# rj45UsbBreakout.net
KiCad netlist of a schematic drawn in EAGLE
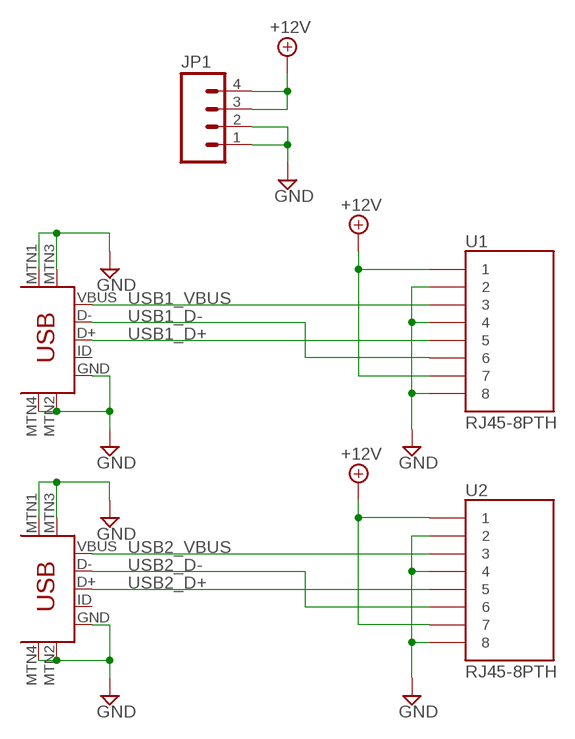
[diagram p0: schematic, sheet 1]

(export (version "E")
  (design (tool "Eeschema 10.0.6"))
  (components
    (comp (ref "JP1")
      (value "M04LOCK")
      (footprint "eagle-import:1X04_LOCK")
      (libsource (lib "eagle-import") (part "M04LOCK"))
    )
    (comp (ref "U1")
      (value "RJ45-8PTH")
      (footprint "eagle-import:RJ45-8")
      (libsource (lib "eagle-import") (part "RJ45-8PTH"))
    )
    (comp (ref "U2")
      (value "RJ45-8PTH")
      (footprint "eagle-import:RJ45-8")
      (libsource (lib "eagle-import") (part "RJ45-8PTH"))
    )
    (comp (ref "U3")
      (value "USB-MINIB-5PIN")
      (footprint "eagle-import:USB-MINIB")
      (libsource (lib "eagle-import") (part "USB-MINIB-5PIN"))
    )
    (comp (ref "U4")
      (value "USB-MINIB-5PIN")
      (footprint "eagle-import:USB-MINIB")
      (libsource (lib "eagle-import") (part "USB-MINIB-5PIN"))
    )
  )
  (nets
    (net (code "1") (name "+12V") (class "Default")
      (node (ref "JP1") (pin "3") (pinfunction "3_3") (pintype "passive"))
      (node (ref "JP1") (pin "4") (pinfunction "4_4") (pintype "passive"))
      (node (ref "U1") (pin "1") (pinfunction "1_1") (pintype "bidirectional"))
      (node (ref "U1") (pin "7") (pinfunction "7_7") (pintype "bidirectional"))
      (node (ref "U2") (pin "1") (pinfunction "1_1") (pintype "bidirectional"))
      (node (ref "U2") (pin "7") (pinfunction "7_7") (pintype "bidirectional"))
    )
    (net (code "2") (name "/USB1_D+") (class "Default")
      (node (ref "U1") (pin "5") (pinfunction "5_5") (pintype "bidirectional"))
      (node (ref "U3") (pin "D+") (pinfunction "D+_D+") (pintype "bidirectional"))
    )
    (net (code "3") (name "/USB1_D-") (class "Default")
      (node (ref "U1") (pin "6") (pinfunction "6_6") (pintype "bidirectional"))
      (node (ref "U3") (pin "D-") (pinfunction "D-_D-") (pintype "bidirectional"))
    )
    (net (code "4") (name "/USB1_VBUS") (class "Default")
      (node (ref "U1") (pin "3") (pinfunction "3_3") (pintype "bidirectional"))
      (node (ref "U3") (pin "VBUS") (pinfunction "VBUS_VBUS") (pintype "bidirectional"))
    )
    (net (code "5") (name "/USB2_D+") (class "Default")
      (node (ref "U2") (pin "5") (pinfunction "5_5") (pintype "bidirectional"))
      (node (ref "U4") (pin "D+") (pinfunction "D+_D+") (pintype "bidirectional"))
    )
    (net (code "6") (name "/USB2_D-") (class "Default")
      (node (ref "U2") (pin "6") (pinfunction "6_6") (pintype "bidirectional"))
      (node (ref "U4") (pin "D-") (pinfunction "D-_D-") (pintype "bidirectional"))
    )
    (net (code "7") (name "/USB2_VBUS") (class "Default")
      (node (ref "U2") (pin "3") (pinfunction "3_3") (pintype "bidirectional"))
      (node (ref "U4") (pin "VBUS") (pinfunction "VBUS_VBUS") (pintype "bidirectional"))
    )
    (net (code "8") (name "GND") (class "Default")
      (node (ref "JP1") (pin "1") (pinfunction "1_1") (pintype "passive"))
      (node (ref "JP1") (pin "2") (pinfunction "2_2") (pintype "passive"))
      (node (ref "U1") (pin "2") (pinfunction "2_2") (pintype "bidirectional"))
      (node (ref "U1") (pin "4") (pinfunction "4_4") (pintype "bidirectional"))
      (node (ref "U1") (pin "8") (pinfunction "8_8") (pintype "bidirectional"))
      (node (ref "U2") (pin "2") (pinfunction "2_2") (pintype "bidirectional"))
      (node (ref "U2") (pin "4") (pinfunction "4_4") (pintype "bidirectional"))
      (node (ref "U2") (pin "8") (pinfunction "8_8") (pintype "bidirectional"))
      (node (ref "U3") (pin "GND") (pinfunction "GND_GND") (pintype "bidirectional"))
      (node (ref "U3") (pin "MTN1") (pinfunction "MTN2_MTN1") (pintype "bidirectional"))
      (node (ref "U3") (pin "MTN2") (pinfunction "MTN3_MTN2") (pintype "bidirectional"))
      (node (ref "U3") (pin "MTN3") (pinfunction "MTN1_MTN3") (pintype "bidirectional"))
      (node (ref "U3") (pin "MTN4") (pinfunction "MTN4_MTN4") (pintype "bidirectional"))
      (node (ref "U4") (pin "GND") (pinfunction "GND_GND") (pintype "bidirectional"))
      (node (ref "U4") (pin "MTN1") (pinfunction "MTN2_MTN1") (pintype "bidirectional"))
      (node (ref "U4") (pin "MTN2") (pinfunction "MTN3_MTN2") (pintype "bidirectional"))
      (node (ref "U4") (pin "MTN3") (pinfunction "MTN1_MTN3") (pintype "bidirectional"))
      (node (ref "U4") (pin "MTN4") (pinfunction "MTN4_MTN4") (pintype "bidirectional"))
    )
    (net (code "9") (name "unconnected-(U3-PadID)") (class "Default")
      (node (ref "U3") (pin "ID") (pinfunction "ID_ID") (pintype "bidirectional"))
    )
    (net (code "10") (name "unconnected-(U4-PadID)") (class "Default")
      (node (ref "U4") (pin "ID") (pinfunction "ID_ID") (pintype "bidirectional"))
    )
  )
)
